# Power.net
KiCad netlist of a schematic drawn in Altium Designer
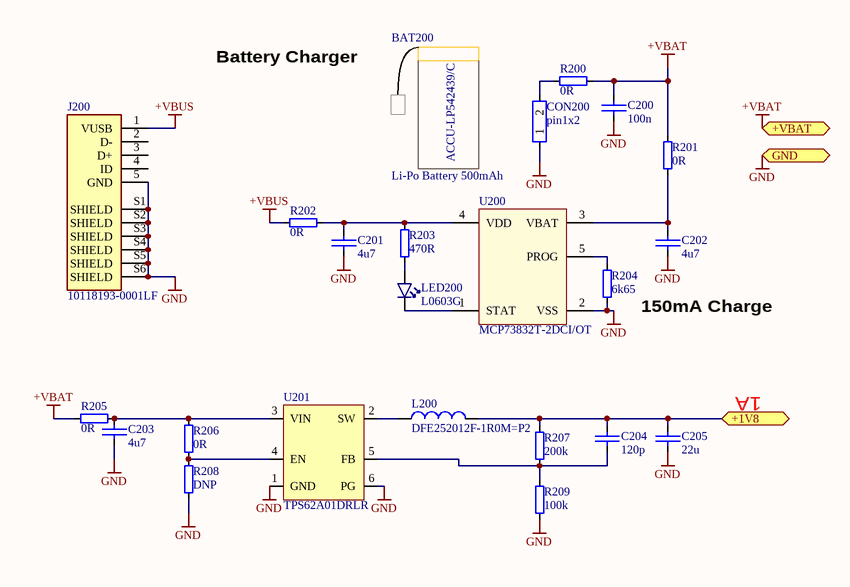
[diagram p0: Power.SchDoc]

(export (version "E")
  (design (tool "Eeschema 10.0.6"))
  (components
    (comp (ref "BAT200")
      (value "Li-Po Battery 500mAh")
      (footprint "Battery 500maH")
      (description "ACCU-LP542439/C")
      (libsource (lib "GPS_LIB_SCH") (part "Li-Po Battery 500mAh"))
    )
    (comp (ref "C200")
      (value "100n")
      (footprint "0402_C")
      (description "Capacitor")
      (libsource (lib "ECS_AMC_all_2016") (part "CAP"))
    )
    (comp (ref "C201")
      (value "4u7")
      (footprint "0603_C")
      (description "Capacitor")
      (libsource (lib "ECS_AMC_all_2016") (part "CAP"))
    )
    (comp (ref "C202")
      (value "4u7")
      (footprint "0603_C")
      (description "Capacitor")
      (libsource (lib "ECS_AMC_all_2016") (part "CAP"))
    )
    (comp (ref "C203")
      (value "4u7")
      (footprint "0603_C")
      (description "Capacitor")
      (libsource (lib "ECS_AMC_all_2016") (part "CAP"))
    )
    (comp (ref "C204")
      (value "120p")
      (footprint "0402_C")
      (description "Capacitor")
      (libsource (lib "ECS_AMC_all_2016") (part "CAP"))
    )
    (comp (ref "C205")
      (value "22u")
      (footprint "0805_c")
      (description "Capacitor")
      (libsource (lib "ECS_AMC_all_2016") (part "CAP"))
    )
    (comp (ref "CON200")
      (value "pin1x2")
      (footprint "piny1x2")
      (description "1x2")
      (libsource (lib "ECS_AMC_all_2016") (part "pin1x2"))
    )
    (comp (ref "J200")
      (value "10118193-0001LF")
      (footprint "FCI_10118193-0001LF")
      (description "USB - micro B USB 2.0 Receptacle Connector 5 Position Surface Mount, Right Angle; Through Hole")
      (fields (field (name "MF") "Amphenol ICC"))
      (libsource (lib "GPS_LIB_SCH") (part "10118193-0001LF"))
    )
    (comp (ref "L200")
      (value "DFE252012F-1R0M=P2")
      (footprint "INDC2520X120N")
      (description "Inductor with Inductance: 1uH Tol. +/-20%, Package: 1008 _2520_")
      (fields (field (name "MF") "Murata Electronics") (field (name "DIGI-KEY_PART_NUMBER") "490-13053-1-ND"))
      (libsource (lib "GPS_LIB_SCH") (part "DFE252012F-1R0M=P2"))
    )
    (comp (ref "LED200")
      (value "L0603G")
      (footprint "LED_0603_G")
      (description "LED, Green, 0603, 573nm, Vf=2.0V, 24mcd, - 40 to +85°C")
      (fields
        (field (name "PART NUMBER") "VS 25C7M5")
        (field (name "MANUFACTURER") "Victory Electronics")
        (field (name "PUBLISHER") "Nordic Semiconductor")
      )
      (libsource (lib "ECS_AMC_all_2016") (part "D{colon}LED"))
    )
    (comp (ref "R200") (value "0R") (footprint "0603") (libsource (lib "") (part "RES_1")))
    (comp (ref "R201") (value "0R") (footprint "0603") (libsource (lib "ECS_AMC_all_2016") (part "RES")))
    (comp (ref "R202") (value "0R") (footprint "0603") (libsource (lib "") (part "RES_1")))
    (comp (ref "R203") (value "470R") (footprint "0603") (libsource (lib "ECS_AMC_all_2016") (part "RES")))
    (comp (ref "R204") (value "6k65") (footprint "0603") (libsource (lib "ECS_AMC_all_2016") (part "RES")))
    (comp (ref "R205") (value "0R") (footprint "0603") (libsource (lib "") (part "RES_1")))
    (comp (ref "R206") (value "0R") (footprint "0603") (libsource (lib "ECS_AMC_all_2016") (part "RES")))
    (comp (ref "R207") (value "200k") (footprint "0603") (libsource (lib "ECS_AMC_all_2016") (part "RES")))
    (comp (ref "R208") (value "DNP") (footprint "0603") (libsource (lib "ECS_AMC_all_2016") (part "RES")))
    (comp (ref "R209") (value "100k") (footprint "0603") (libsource (lib "ECS_AMC_all_2016") (part "RES")))
    (comp (ref "U200")
      (value "MCP73832T-2DCI/OT")
      (footprint "SOT95P280X145-5N")
      (description "Charger IC Lithium Ion/Polymer SOT-23-5")
      (fields (field (name "MF") "Microchip"))
      (libsource (lib "GPS_LIB_SCH") (part "MCP73832T-2DCI/OT"))
    )
    (comp (ref "U201")
      (value "TPS62A01DRLR")
      (footprint "TPS62A01DRLR")
      (libsource (lib "GPS_LIB_SCH") (part "TPS62A01DRLR"))
    )
  )
  (nets
    (net (code "1") (name "+VBAT") (class "Default")
      (node (ref "C200") (pin "2") (pinfunction "2_2") (pintype "passive"))
      (node (ref "R200") (pin "1") (pinfunction "1_1") (pintype "passive"))
      (node (ref "R201") (pin "1") (pinfunction "1_1") (pintype "passive"))
      (node (ref "R205") (pin "2") (pinfunction "2_2") (pintype "passive"))
    )
    (net (code "2") (name "+VBUS") (class "Default")
      (node (ref "J200") (pin "1") (pinfunction "VUSB_1") (pintype "passive"))
      (node (ref "R202") (pin "2") (pinfunction "2_2") (pintype "passive"))
    )
    (net (code "3") (name "/+1V8") (class "Default")
      (node (ref "C204") (pin "2") (pinfunction "2_2") (pintype "passive"))
      (node (ref "C205") (pin "2") (pinfunction "2_2") (pintype "passive"))
      (node (ref "L200") (pin "2") (pinfunction "2_2") (pintype "passive"))
      (node (ref "R207") (pin "1") (pinfunction "1_1") (pintype "passive"))
    )
    (net (code "4") (name "GND") (class "Default")
      (node (ref "C200") (pin "1") (pinfunction "1_1") (pintype "passive"))
      (node (ref "C201") (pin "1") (pinfunction "1_1") (pintype "passive"))
      (node (ref "C202") (pin "1") (pinfunction "1_1") (pintype "passive"))
      (node (ref "C203") (pin "1") (pinfunction "1_1") (pintype "passive"))
      (node (ref "C205") (pin "1") (pinfunction "1_1") (pintype "passive"))
      (node (ref "CON200") (pin "1") (pinfunction "1_1") (pintype "passive"))
      (node (ref "J200") (pin "5") (pinfunction "GND_5") (pintype "passive"))
      (node (ref "J200") (pin "S1") (pinfunction "SHIELD_S1") (pintype "passive"))
      (node (ref "J200") (pin "S2") (pinfunction "SHIELD_S2") (pintype "passive"))
      (node (ref "J200") (pin "S3") (pinfunction "SHIELD_S3") (pintype "passive"))
      (node (ref "J200") (pin "S4") (pinfunction "SHIELD_S4") (pintype "passive"))
      (node (ref "J200") (pin "S5") (pinfunction "SHIELD_S5") (pintype "passive"))
      (node (ref "J200") (pin "S6") (pinfunction "SHIELD_S6") (pintype "passive"))
      (node (ref "R204") (pin "2") (pinfunction "2_2") (pintype "passive"))
      (node (ref "R208") (pin "2") (pinfunction "2_2") (pintype "passive"))
      (node (ref "R209") (pin "2") (pinfunction "2_2") (pintype "passive"))
      (node (ref "U200") (pin "2") (pinfunction "VSS_2") (pintype "passive"))
      (node (ref "U201") (pin "1") (pinfunction "GND_1") (pintype "passive"))
      (node (ref "U201") (pin "6") (pinfunction "PG_6") (pintype "passive"))
    )
    (net (code "5") (name "Net-(CON200-Pad2)") (class "Default")
      (node (ref "CON200") (pin "2") (pinfunction "2_2") (pintype "passive"))
      (node (ref "R200") (pin "2") (pinfunction "2_2") (pintype "passive"))
    )
    (net (code "6") (name "Net-(LED200-A)") (class "Default")
      (node (ref "LED200") (pin "2") (pinfunction "A_2") (pintype "passive"))
      (node (ref "R203") (pin "2") (pinfunction "2_2") (pintype "passive"))
    )
    (net (code "7") (name "Net-(LED200-C)") (class "Default")
      (node (ref "LED200") (pin "1") (pinfunction "C_1") (pintype "passive"))
      (node (ref "U200") (pin "1") (pinfunction "STAT_1") (pintype "passive"))
    )
    (net (code "8") (name "Net-(U200-PROG)") (class "Default")
      (node (ref "R204") (pin "1") (pinfunction "1_1") (pintype "passive"))
      (node (ref "U200") (pin "5") (pinfunction "PROG_5") (pintype "passive"))
    )
    (net (code "9") (name "Net-(U200-VBAT)") (class "Default")
      (node (ref "C202") (pin "2") (pinfunction "2_2") (pintype "passive"))
      (node (ref "R201") (pin "2") (pinfunction "2_2") (pintype "passive"))
      (node (ref "U200") (pin "3") (pinfunction "VBAT_3") (pintype "passive"))
    )
    (net (code "10") (name "Net-(U200-VDD)") (class "Default")
      (node (ref "C201") (pin "2") (pinfunction "2_2") (pintype "passive"))
      (node (ref "R202") (pin "1") (pinfunction "1_1") (pintype "passive"))
      (node (ref "R203") (pin "1") (pinfunction "1_1") (pintype "passive"))
      (node (ref "U200") (pin "4") (pinfunction "VDD_4") (pintype "passive"))
    )
    (net (code "11") (name "Net-(U201-EN)") (class "Default")
      (node (ref "R206") (pin "2") (pinfunction "2_2") (pintype "passive"))
      (node (ref "R208") (pin "1") (pinfunction "1_1") (pintype "passive"))
      (node (ref "U201") (pin "4") (pinfunction "EN_4") (pintype "passive"))
    )
    (net (code "12") (name "Net-(U201-FB)") (class "Default")
      (node (ref "C204") (pin "1") (pinfunction "1_1") (pintype "passive"))
      (node (ref "R207") (pin "2") (pinfunction "2_2") (pintype "passive"))
      (node (ref "R209") (pin "1") (pinfunction "1_1") (pintype "passive"))
      (node (ref "U201") (pin "5") (pinfunction "FB_5") (pintype "passive"))
    )
    (net (code "13") (name "Net-(U201-SW)") (class "Default")
      (node (ref "L200") (pin "1") (pinfunction "1_1") (pintype "passive"))
      (node (ref "U201") (pin "2") (pinfunction "SW_2") (pintype "passive"))
    )
    (net (code "14") (name "Net-(U201-VIN)") (class "Default")
      (node (ref "C203") (pin "2") (pinfunction "2_2") (pintype "passive"))
      (node (ref "R205") (pin "1") (pinfunction "1_1") (pintype "passive"))
      (node (ref "R206") (pin "1") (pinfunction "1_1") (pintype "passive"))
      (node (ref "U201") (pin "3") (pinfunction "VIN_3") (pintype "passive"))
    )
    (net (code "15") (name "unconnected-(J200-D+-Pad3)") (class "Default")
      (node (ref "J200") (pin "3") (pinfunction "D+_3") (pintype "passive"))
    )
    (net (code "16") (name "unconnected-(J200-D--Pad2)") (class "Default")
      (node (ref "J200") (pin "2") (pinfunction "D-_2") (pintype "passive"))
    )
    (net (code "17") (name "unconnected-(J200-ID-Pad4)") (class "Default")
      (node (ref "J200") (pin "4") (pinfunction "ID_4") (pintype "passive"))
    )
  )
)
